# EncoderTBPCB.net
KiCad netlist of a schematic drawn in EAGLE
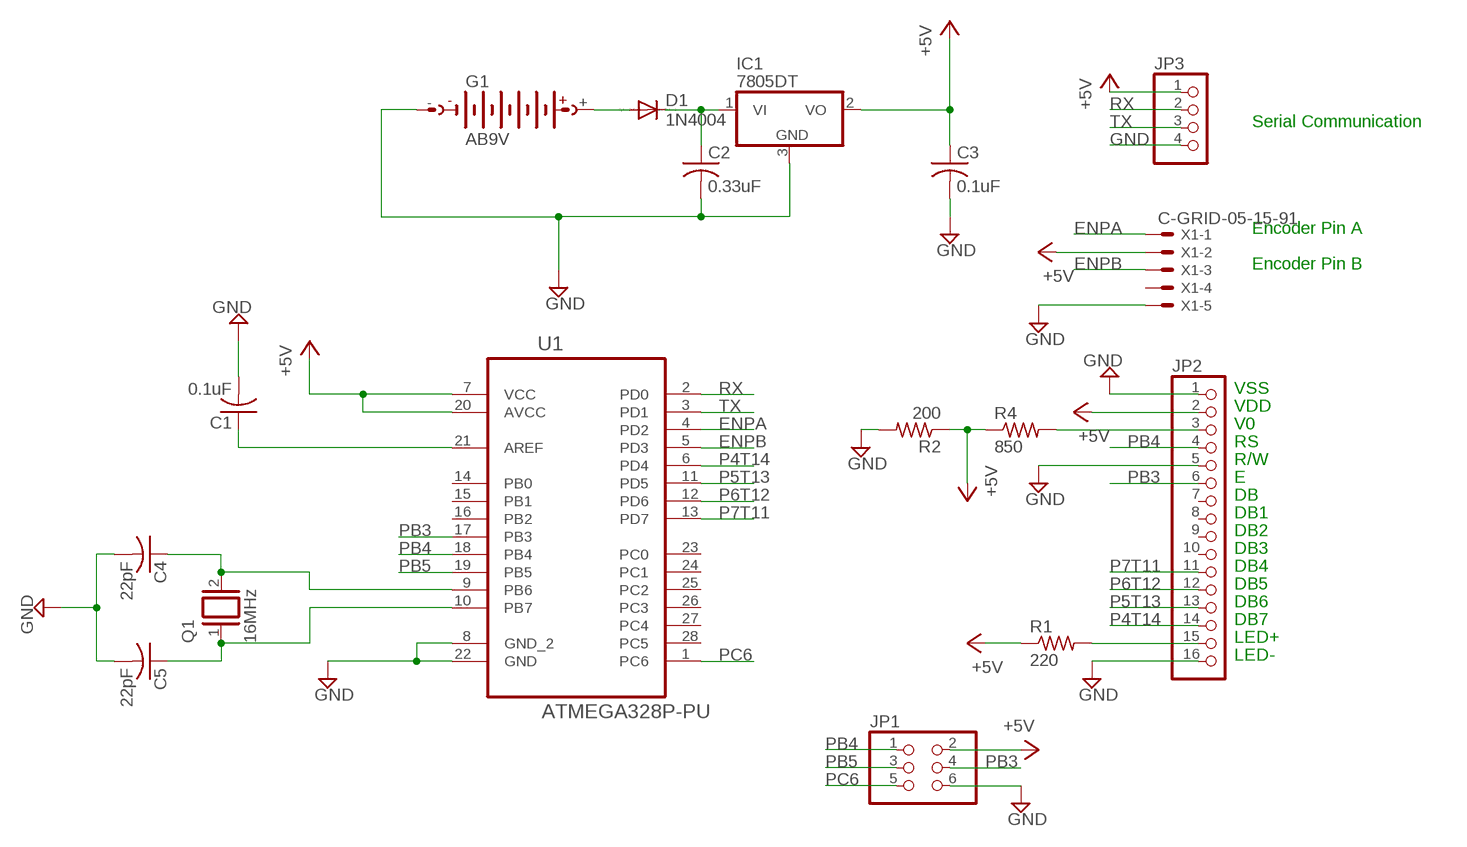
[diagram p0: schematic, sheet 1]

(export (version "E")
  (design (tool "Eeschema 10.0.6"))
  (components
    (comp (ref "C1")
      (value "0.1uF")
      (footprint "eagle-import:C0603")
      (libsource (lib "eagle-import") (part "C-USC0603"))
    )
    (comp (ref "C2")
      (value "0.33uF")
      (footprint "eagle-import:C0603")
      (libsource (lib "eagle-import") (part "C-USC0603"))
    )
    (comp (ref "C3")
      (value "0.1uF")
      (footprint "eagle-import:C0603")
      (libsource (lib "eagle-import") (part "C-USC0603"))
    )
    (comp (ref "C4")
      (value "22pF")
      (footprint "eagle-import:C0603")
      (libsource (lib "eagle-import") (part "C-USC0603"))
    )
    (comp (ref "C5")
      (value "22pF")
      (footprint "eagle-import:C0603")
      (libsource (lib "eagle-import") (part "C-USC0603"))
    )
    (comp (ref "D1")
      (value "1N4004")
      (footprint "eagle-import:DO41-10")
      (libsource (lib "eagle-import") (part "1N4004"))
    )
    (comp (ref "G1")
      (value "AB9V")
      (footprint "eagle-import:AB9V")
      (libsource (lib "eagle-import") (part "AB9V"))
    )
    (comp (ref "IC1")
      (value "7805DT")
      (footprint "eagle-import:TO252")
      (libsource (lib "eagle-import") (part "78DT05"))
    )
    (comp (ref "JP1")
      (value "PINHD-2X3")
      (footprint "eagle-import:2X03")
      (libsource (lib "eagle-import") (part "PINHD-2X3"))
    )
    (comp (ref "JP2")
      (value "PINHD-1X16")
      (footprint "eagle-import:1X16")
      (libsource (lib "eagle-import") (part "PINHD-1X16"))
    )
    (comp (ref "JP3")
      (value "PINHD-1X4")
      (footprint "eagle-import:1X04")
      (libsource (lib "eagle-import") (part "PINHD-1X4"))
    )
    (comp (ref "Q1")
      (value "16MHz")
      (footprint "eagle-import:QS")
      (libsource (lib "eagle-import") (part "XTAL/S"))
    )
    (comp (ref "R1")
      (value "220")
      (footprint "eagle-import:R0603")
      (libsource (lib "eagle-import") (part "R-US_R0603"))
    )
    (comp (ref "R2")
      (value "200")
      (footprint "eagle-import:R0603")
      (libsource (lib "eagle-import") (part "R-US_R0603"))
    )
    (comp (ref "R4")
      (value "850")
      (footprint "eagle-import:R0603")
      (libsource (lib "eagle-import") (part "R-US_R0603"))
    )
    (comp (ref "U1")
      (value "ATMEGA328P-PU")
      (footprint "eagle-import:DIP254P762X457-28")
      (libsource (lib "eagle-import") (part "ATMEGA328P-PU"))
    )
    (comp (ref "X1")
      (value "C-GRID-05-15-91")
      (footprint "eagle-import:15-91-05")
      (libsource (lib "eagle-import") (part "C-GRID-05-15-91"))
    )
  )
  (nets
    (net (code "1") (name "+5V") (class "Default")
      (node (ref "C3") (pin "1") (pinfunction "1_1") (pintype "passive"))
      (node (ref "IC1") (pin "2") (pinfunction "VO_2") (pintype "passive"))
      (node (ref "JP1") (pin "2") (pinfunction "2_2") (pintype "passive"))
      (node (ref "JP2") (pin "2") (pinfunction "2_2") (pintype "passive"))
      (node (ref "JP3") (pin "1") (pinfunction "1_1") (pintype "passive"))
      (node (ref "R1") (pin "1") (pinfunction "1_1") (pintype "passive"))
      (node (ref "R2") (pin "1") (pinfunction "1_1") (pintype "passive"))
      (node (ref "R4") (pin "1") (pinfunction "1_1") (pintype "passive"))
      (node (ref "U1") (pin "20") (pinfunction "AVCC_20") (pintype "power_in"))
      (node (ref "U1") (pin "7") (pinfunction "VCC_7") (pintype "power_in"))
      (node (ref "X1") (pin "2") (pinfunction "S_2") (pintype "passive"))
    )
    (net (code "2") (name "/ENPA") (class "Default")
      (node (ref "U1") (pin "4") (pinfunction "PD2_4") (pintype "bidirectional"))
      (node (ref "X1") (pin "1") (pinfunction "S_1") (pintype "passive"))
    )
    (net (code "3") (name "/ENPB") (class "Default")
      (node (ref "U1") (pin "5") (pinfunction "PD3_5") (pintype "bidirectional"))
      (node (ref "X1") (pin "3") (pinfunction "S_3") (pintype "passive"))
    )
    (net (code "4") (name "/P4T14") (class "Default")
      (node (ref "JP2") (pin "14") (pinfunction "14_14") (pintype "passive"))
      (node (ref "U1") (pin "6") (pinfunction "PD4_6") (pintype "bidirectional"))
    )
    (net (code "5") (name "/P5T13") (class "Default")
      (node (ref "JP2") (pin "13") (pinfunction "13_13") (pintype "passive"))
      (node (ref "U1") (pin "11") (pinfunction "PD5_11") (pintype "bidirectional"))
    )
    (net (code "6") (name "/P6T12") (class "Default")
      (node (ref "JP2") (pin "12") (pinfunction "12_12") (pintype "passive"))
      (node (ref "U1") (pin "12") (pinfunction "PD6_12") (pintype "bidirectional"))
    )
    (net (code "7") (name "/P7T11") (class "Default")
      (node (ref "JP2") (pin "11") (pinfunction "11_11") (pintype "passive"))
      (node (ref "U1") (pin "13") (pinfunction "PD7_13") (pintype "bidirectional"))
    )
    (net (code "8") (name "/PB3") (class "Default")
      (node (ref "JP1") (pin "4") (pinfunction "4_4") (pintype "passive"))
      (node (ref "JP2") (pin "6") (pinfunction "6_6") (pintype "passive"))
      (node (ref "U1") (pin "17") (pinfunction "PB3_17") (pintype "bidirectional"))
    )
    (net (code "9") (name "/PB4") (class "Default")
      (node (ref "JP1") (pin "1") (pinfunction "1_1") (pintype "passive"))
      (node (ref "JP2") (pin "4") (pinfunction "4_4") (pintype "passive"))
      (node (ref "U1") (pin "18") (pinfunction "PB4_18") (pintype "bidirectional"))
    )
    (net (code "10") (name "/PB5") (class "Default")
      (node (ref "JP1") (pin "3") (pinfunction "3_3") (pintype "passive"))
      (node (ref "U1") (pin "19") (pinfunction "PB5_19") (pintype "bidirectional"))
    )
    (net (code "11") (name "/PC6") (class "Default")
      (node (ref "JP1") (pin "5") (pinfunction "5_5") (pintype "passive"))
      (node (ref "U1") (pin "1") (pinfunction "PC6_1") (pintype "bidirectional"))
    )
    (net (code "12") (name "/RX") (class "Default")
      (node (ref "JP3") (pin "2") (pinfunction "2_2") (pintype "passive"))
      (node (ref "U1") (pin "2") (pinfunction "PD0_2") (pintype "bidirectional"))
    )
    (net (code "13") (name "/TX") (class "Default")
      (node (ref "JP3") (pin "3") (pinfunction "3_3") (pintype "passive"))
      (node (ref "U1") (pin "3") (pinfunction "PD1_3") (pintype "bidirectional"))
    )
    (net (code "14") (name "GND") (class "Default")
      (node (ref "C1") (pin "2") (pinfunction "2_2") (pintype "passive"))
      (node (ref "C2") (pin "2") (pinfunction "2_2") (pintype "passive"))
      (node (ref "C3") (pin "2") (pinfunction "2_2") (pintype "passive"))
      (node (ref "C4") (pin "2") (pinfunction "2_2") (pintype "passive"))
      (node (ref "C5") (pin "2") (pinfunction "2_2") (pintype "passive"))
      (node (ref "G1") (pin "-") (pinfunction "-_-") (pintype "passive"))
      (node (ref "IC1") (pin "3") (pinfunction "GND_3") (pintype "passive"))
      (node (ref "JP1") (pin "6") (pinfunction "6_6") (pintype "passive"))
      (node (ref "JP2") (pin "1") (pinfunction "1_1") (pintype "passive"))
      (node (ref "JP2") (pin "16") (pinfunction "16_16") (pintype "passive"))
      (node (ref "JP2") (pin "5") (pinfunction "5_5") (pintype "passive"))
      (node (ref "JP3") (pin "4") (pinfunction "4_4") (pintype "passive"))
      (node (ref "R2") (pin "2") (pinfunction "2_2") (pintype "passive"))
      (node (ref "U1") (pin "22") (pinfunction "GND_22") (pintype "passive"))
      (node (ref "U1") (pin "8") (pinfunction "GND_2_8") (pintype "passive"))
      (node (ref "X1") (pin "5") (pinfunction "S_5") (pintype "passive"))
    )
    (net (code "15") (name "Net-(D1-PadA)") (class "Default")
      (node (ref "D1") (pin "A") (pinfunction "A_A") (pintype "passive"))
      (node (ref "G1") (pin "+") (pinfunction "+_+") (pintype "passive"))
    )
    (net (code "16") (name "Net-(IC1-VI)") (class "Default")
      (node (ref "C2") (pin "1") (pinfunction "1_1") (pintype "passive"))
      (node (ref "D1") (pin "C") (pinfunction "C_C") (pintype "passive"))
      (node (ref "IC1") (pin "1") (pinfunction "VI_1") (pintype "input"))
    )
    (net (code "17") (name "Net-(JP2-Pad3)") (class "Default")
      (node (ref "JP2") (pin "3") (pinfunction "3_3") (pintype "passive"))
      (node (ref "R4") (pin "2") (pinfunction "2_2") (pintype "passive"))
    )
    (net (code "18") (name "Net-(JP2-Pad15)") (class "Default")
      (node (ref "JP2") (pin "15") (pinfunction "15_15") (pintype "passive"))
      (node (ref "R1") (pin "2") (pinfunction "2_2") (pintype "passive"))
    )
    (net (code "19") (name "Net-(U1-AREF)") (class "Default")
      (node (ref "C1") (pin "1") (pinfunction "1_1") (pintype "passive"))
      (node (ref "U1") (pin "21") (pinfunction "AREF_21") (pintype "input"))
    )
    (net (code "20") (name "Net-(U1-PB6)") (class "Default")
      (node (ref "C4") (pin "1") (pinfunction "1_1") (pintype "passive"))
      (node (ref "Q1") (pin "2") (pinfunction "2_2") (pintype "passive"))
      (node (ref "U1") (pin "9") (pinfunction "PB6_9") (pintype "bidirectional"))
    )
    (net (code "21") (name "Net-(U1-PB7)") (class "Default")
      (node (ref "C5") (pin "1") (pinfunction "1_1") (pintype "passive"))
      (node (ref "Q1") (pin "1") (pinfunction "1_1") (pintype "passive"))
      (node (ref "U1") (pin "10") (pinfunction "PB7_10") (pintype "bidirectional"))
    )
    (net (code "22") (name "unconnected-(JP2-Pad7)") (class "Default")
      (node (ref "JP2") (pin "7") (pinfunction "7_7") (pintype "passive"))
    )
    (net (code "23") (name "unconnected-(JP2-Pad8)") (class "Default")
      (node (ref "JP2") (pin "8") (pinfunction "8_8") (pintype "passive"))
    )
    (net (code "24") (name "unconnected-(JP2-Pad9)") (class "Default")
      (node (ref "JP2") (pin "9") (pinfunction "9_9") (pintype "passive"))
    )
    (net (code "25") (name "unconnected-(JP2-Pad10)") (class "Default")
      (node (ref "JP2") (pin "10") (pinfunction "10_10") (pintype "passive"))
    )
    (net (code "26") (name "unconnected-(U1-PB0-Pad14)") (class "Default")
      (node (ref "U1") (pin "14") (pinfunction "PB0_14") (pintype "bidirectional"))
    )
    (net (code "27") (name "unconnected-(U1-PB1-Pad15)") (class "Default")
      (node (ref "U1") (pin "15") (pinfunction "PB1_15") (pintype "bidirectional"))
    )
    (net (code "28") (name "unconnected-(U1-PB2-Pad16)") (class "Default")
      (node (ref "U1") (pin "16") (pinfunction "PB2_16") (pintype "bidirectional"))
    )
    (net (code "29") (name "unconnected-(U1-PC0-Pad23)") (class "Default")
      (node (ref "U1") (pin "23") (pinfunction "PC0_23") (pintype "bidirectional"))
    )
    (net (code "30") (name "unconnected-(U1-PC1-Pad24)") (class "Default")
      (node (ref "U1") (pin "24") (pinfunction "PC1_24") (pintype "bidirectional"))
    )
    (net (code "31") (name "unconnected-(U1-PC2-Pad25)") (class "Default")
      (node (ref "U1") (pin "25") (pinfunction "PC2_25") (pintype "bidirectional"))
    )
    (net (code "32") (name "unconnected-(U1-PC3-Pad26)") (class "Default")
      (node (ref "U1") (pin "26") (pinfunction "PC3_26") (pintype "bidirectional"))
    )
    (net (code "33") (name "unconnected-(U1-PC4-Pad27)") (class "Default")
      (node (ref "U1") (pin "27") (pinfunction "PC4_27") (pintype "bidirectional"))
    )
    (net (code "34") (name "unconnected-(U1-PC5-Pad28)") (class "Default")
      (node (ref "U1") (pin "28") (pinfunction "PC5_28") (pintype "bidirectional"))
    )
    (net (code "35") (name "unconnected-(X1D-S-Pad4)") (class "Default")
      (node (ref "X1") (pin "4") (pinfunction "S_4") (pintype "passive"))
    )
  )
)
